# sensor_board.net
KiCad netlist of a schematic drawn in Altium Designer
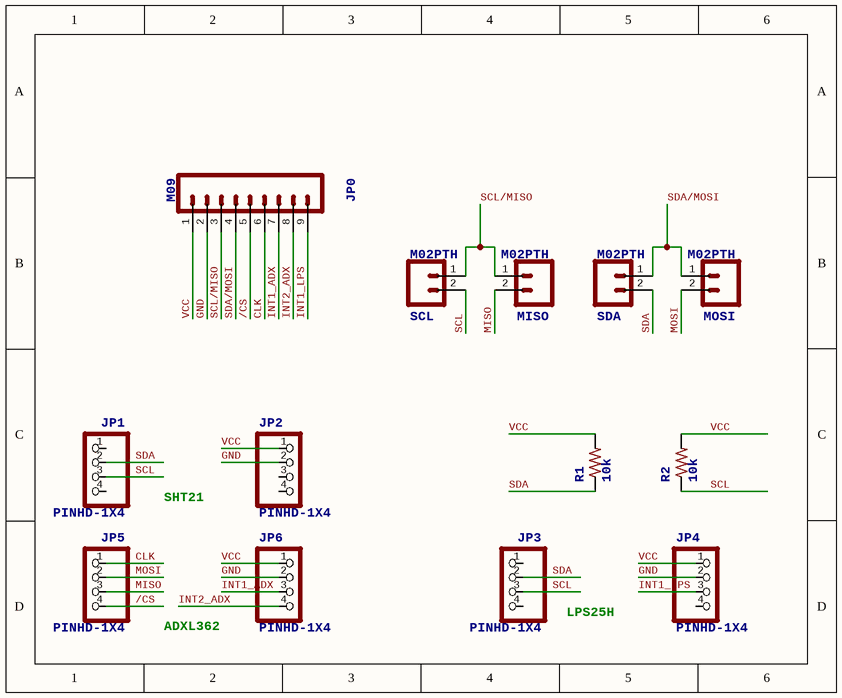
[diagram p0: sensor_board.SchDoc]

(export (version "E")
  (design (tool "Eeschema 10.0.6"))
  (components
    (comp (ref "JP0") (value "M09") (footprint "1X09") (libsource (lib "SparkFun-Connectors") (part "M09")))
    (comp (ref "JP1")
      (value "PINHD-1X4")
      (footprint "1X04")
      (description "<b>PIN HEADER</b>")
      (libsource (lib "pinhead") (part "PINHD-1X4"))
    )
    (comp (ref "JP2")
      (value "PINHD-1X4")
      (footprint "1X04")
      (description "<b>PIN HEADER</b>")
      (libsource (lib "pinhead") (part "PINHD-1X4"))
    )
    (comp (ref "JP3")
      (value "PINHD-1X4")
      (footprint "1X04")
      (description "<b>PIN HEADER</b>")
      (libsource (lib "pinhead") (part "PINHD-1X4"))
    )
    (comp (ref "JP4")
      (value "PINHD-1X4")
      (footprint "1X04")
      (description "<b>PIN HEADER</b>")
      (libsource (lib "pinhead") (part "PINHD-1X4"))
    )
    (comp (ref "JP5")
      (value "PINHD-1X4")
      (footprint "1X04")
      (description "<b>PIN HEADER</b>")
      (libsource (lib "pinhead") (part "PINHD-1X4"))
    )
    (comp (ref "JP6")
      (value "PINHD-1X4")
      (footprint "1X04")
      (description "<b>PIN HEADER</b>")
      (libsource (lib "pinhead") (part "PINHD-1X4"))
    )
    (comp (ref "MISO")
      (value "M02PTH")
      (footprint "1X02")
      (libsource (lib "SparkFun-Connectors") (part "M02PTH"))
    )
    (comp (ref "MOSI")
      (value "M02PTH")
      (footprint "1X02")
      (libsource (lib "SparkFun-Connectors") (part "M02PTH"))
    )
    (comp (ref "R1")
      (value "10k")
      (footprint "AXIAL-0.3")
      (description "RES-09435")
      (libsource (lib "SparkFun-Resistors") (part "10KOHM-1/4W5%(PTH)"))
    )
    (comp (ref "R2")
      (value "10k")
      (footprint "AXIAL-0.3")
      (description "RES-09435")
      (libsource (lib "SparkFun-Resistors") (part "10KOHM-1/4W5%(PTH)"))
    )
    (comp (ref "SCL")
      (value "M02PTH")
      (footprint "1X02")
      (libsource (lib "SparkFun-Connectors") (part "M02PTH"))
    )
    (comp (ref "SDA")
      (value "M02PTH")
      (footprint "1X02")
      (libsource (lib "SparkFun-Connectors") (part "M02PTH"))
    )
  )
  (nets
    (net (code "1") (name "/CLK") (class "Default")
      (node (ref "JP0") (pin "6") (pinfunction "6_6") (pintype "passive"))
      (node (ref "JP5") (pin "1") (pinfunction "1_1") (pintype "passive"))
    )
    (net (code "2") (name "/GND") (class "Default")
      (node (ref "JP0") (pin "2") (pinfunction "2_2") (pintype "passive"))
      (node (ref "JP2") (pin "2") (pinfunction "2_2") (pintype "passive"))
      (node (ref "JP4") (pin "2") (pinfunction "2_2") (pintype "passive"))
      (node (ref "JP6") (pin "2") (pinfunction "2_2") (pintype "passive"))
    )
    (net (code "3") (name "/INT1_ADX") (class "Default")
      (node (ref "JP0") (pin "7") (pinfunction "7_7") (pintype "passive"))
      (node (ref "JP6") (pin "3") (pinfunction "3_3") (pintype "passive"))
    )
    (net (code "4") (name "/INT1_LPS") (class "Default")
      (node (ref "JP0") (pin "9") (pinfunction "9_9") (pintype "passive"))
      (node (ref "JP4") (pin "3") (pinfunction "3_3") (pintype "passive"))
    )
    (net (code "5") (name "/INT2_ADX") (class "Default")
      (node (ref "JP0") (pin "8") (pinfunction "8_8") (pintype "passive"))
      (node (ref "JP6") (pin "4") (pinfunction "4_4") (pintype "passive"))
    )
    (net (code "6") (name "/MISO") (class "Default")
      (node (ref "JP5") (pin "3") (pinfunction "3_3") (pintype "passive"))
      (node (ref "MISO") (pin "2") (pinfunction "2_2") (pintype "passive"))
    )
    (net (code "7") (name "/MOSI") (class "Default")
      (node (ref "JP5") (pin "2") (pinfunction "2_2") (pintype "passive"))
      (node (ref "MOSI") (pin "2") (pinfunction "2_2") (pintype "passive"))
    )
    (net (code "8") (name "/SCL") (class "Default")
      (node (ref "JP1") (pin "3") (pinfunction "3_3") (pintype "passive"))
      (node (ref "JP3") (pin "3") (pinfunction "3_3") (pintype "passive"))
      (node (ref "R2") (pin "P$1") (pinfunction "1_P$1") (pintype "passive"))
      (node (ref "SCL") (pin "2") (pinfunction "2_2") (pintype "passive"))
    )
    (net (code "9") (name "/SCL{slash}MISO") (class "Default")
      (node (ref "JP0") (pin "3") (pinfunction "3_3") (pintype "passive"))
      (node (ref "MISO") (pin "1") (pinfunction "1_1") (pintype "passive"))
      (node (ref "SCL") (pin "1") (pinfunction "1_1") (pintype "passive"))
    )
    (net (code "10") (name "/SDA") (class "Default")
      (node (ref "JP1") (pin "2") (pinfunction "2_2") (pintype "passive"))
      (node (ref "JP3") (pin "2") (pinfunction "2_2") (pintype "passive"))
      (node (ref "R1") (pin "P$1") (pinfunction "1_P$1") (pintype "passive"))
      (node (ref "SDA") (pin "2") (pinfunction "2_2") (pintype "passive"))
    )
    (net (code "11") (name "/SDA{slash}MOSI") (class "Default")
      (node (ref "JP0") (pin "4") (pinfunction "4_4") (pintype "passive"))
      (node (ref "MOSI") (pin "1") (pinfunction "1_1") (pintype "passive"))
      (node (ref "SDA") (pin "1") (pinfunction "1_1") (pintype "passive"))
    )
    (net (code "12") (name "/VCC") (class "Default")
      (node (ref "JP0") (pin "1") (pinfunction "1_1") (pintype "passive"))
      (node (ref "JP2") (pin "1") (pinfunction "1_1") (pintype "passive"))
      (node (ref "JP4") (pin "1") (pinfunction "1_1") (pintype "passive"))
      (node (ref "JP6") (pin "1") (pinfunction "1_1") (pintype "passive"))
      (node (ref "R1") (pin "P$2") (pinfunction "2_P$2") (pintype "passive"))
      (node (ref "R2") (pin "P$2") (pinfunction "2_P$2") (pintype "passive"))
    )
    (net (code "13") (name "/{slash}CS") (class "Default")
      (node (ref "JP0") (pin "5") (pinfunction "5_5") (pintype "passive"))
      (node (ref "JP5") (pin "4") (pinfunction "4_4") (pintype "passive"))
    )
    (net (code "14") (name "unconnected-(JP1-Pad1)") (class "Default")
      (node (ref "JP1") (pin "1") (pinfunction "1_1") (pintype "passive"))
    )
    (net (code "15") (name "unconnected-(JP1-Pad4)") (class "Default")
      (node (ref "JP1") (pin "4") (pinfunction "4_4") (pintype "passive"))
    )
    (net (code "16") (name "unconnected-(JP2-Pad3)") (class "Default")
      (node (ref "JP2") (pin "3") (pinfunction "3_3") (pintype "passive"))
    )
    (net (code "17") (name "unconnected-(JP2-Pad4)") (class "Default")
      (node (ref "JP2") (pin "4") (pinfunction "4_4") (pintype "passive"))
    )
    (net (code "18") (name "unconnected-(JP3-Pad1)") (class "Default")
      (node (ref "JP3") (pin "1") (pinfunction "1_1") (pintype "passive"))
    )
    (net (code "19") (name "unconnected-(JP3-Pad4)") (class "Default")
      (node (ref "JP3") (pin "4") (pinfunction "4_4") (pintype "passive"))
    )
    (net (code "20") (name "unconnected-(JP4-Pad4)") (class "Default")
      (node (ref "JP4") (pin "4") (pinfunction "4_4") (pintype "passive"))
    )
  )
)
